# MotorBoard.net
KiCad netlist of a schematic drawn in EAGLE
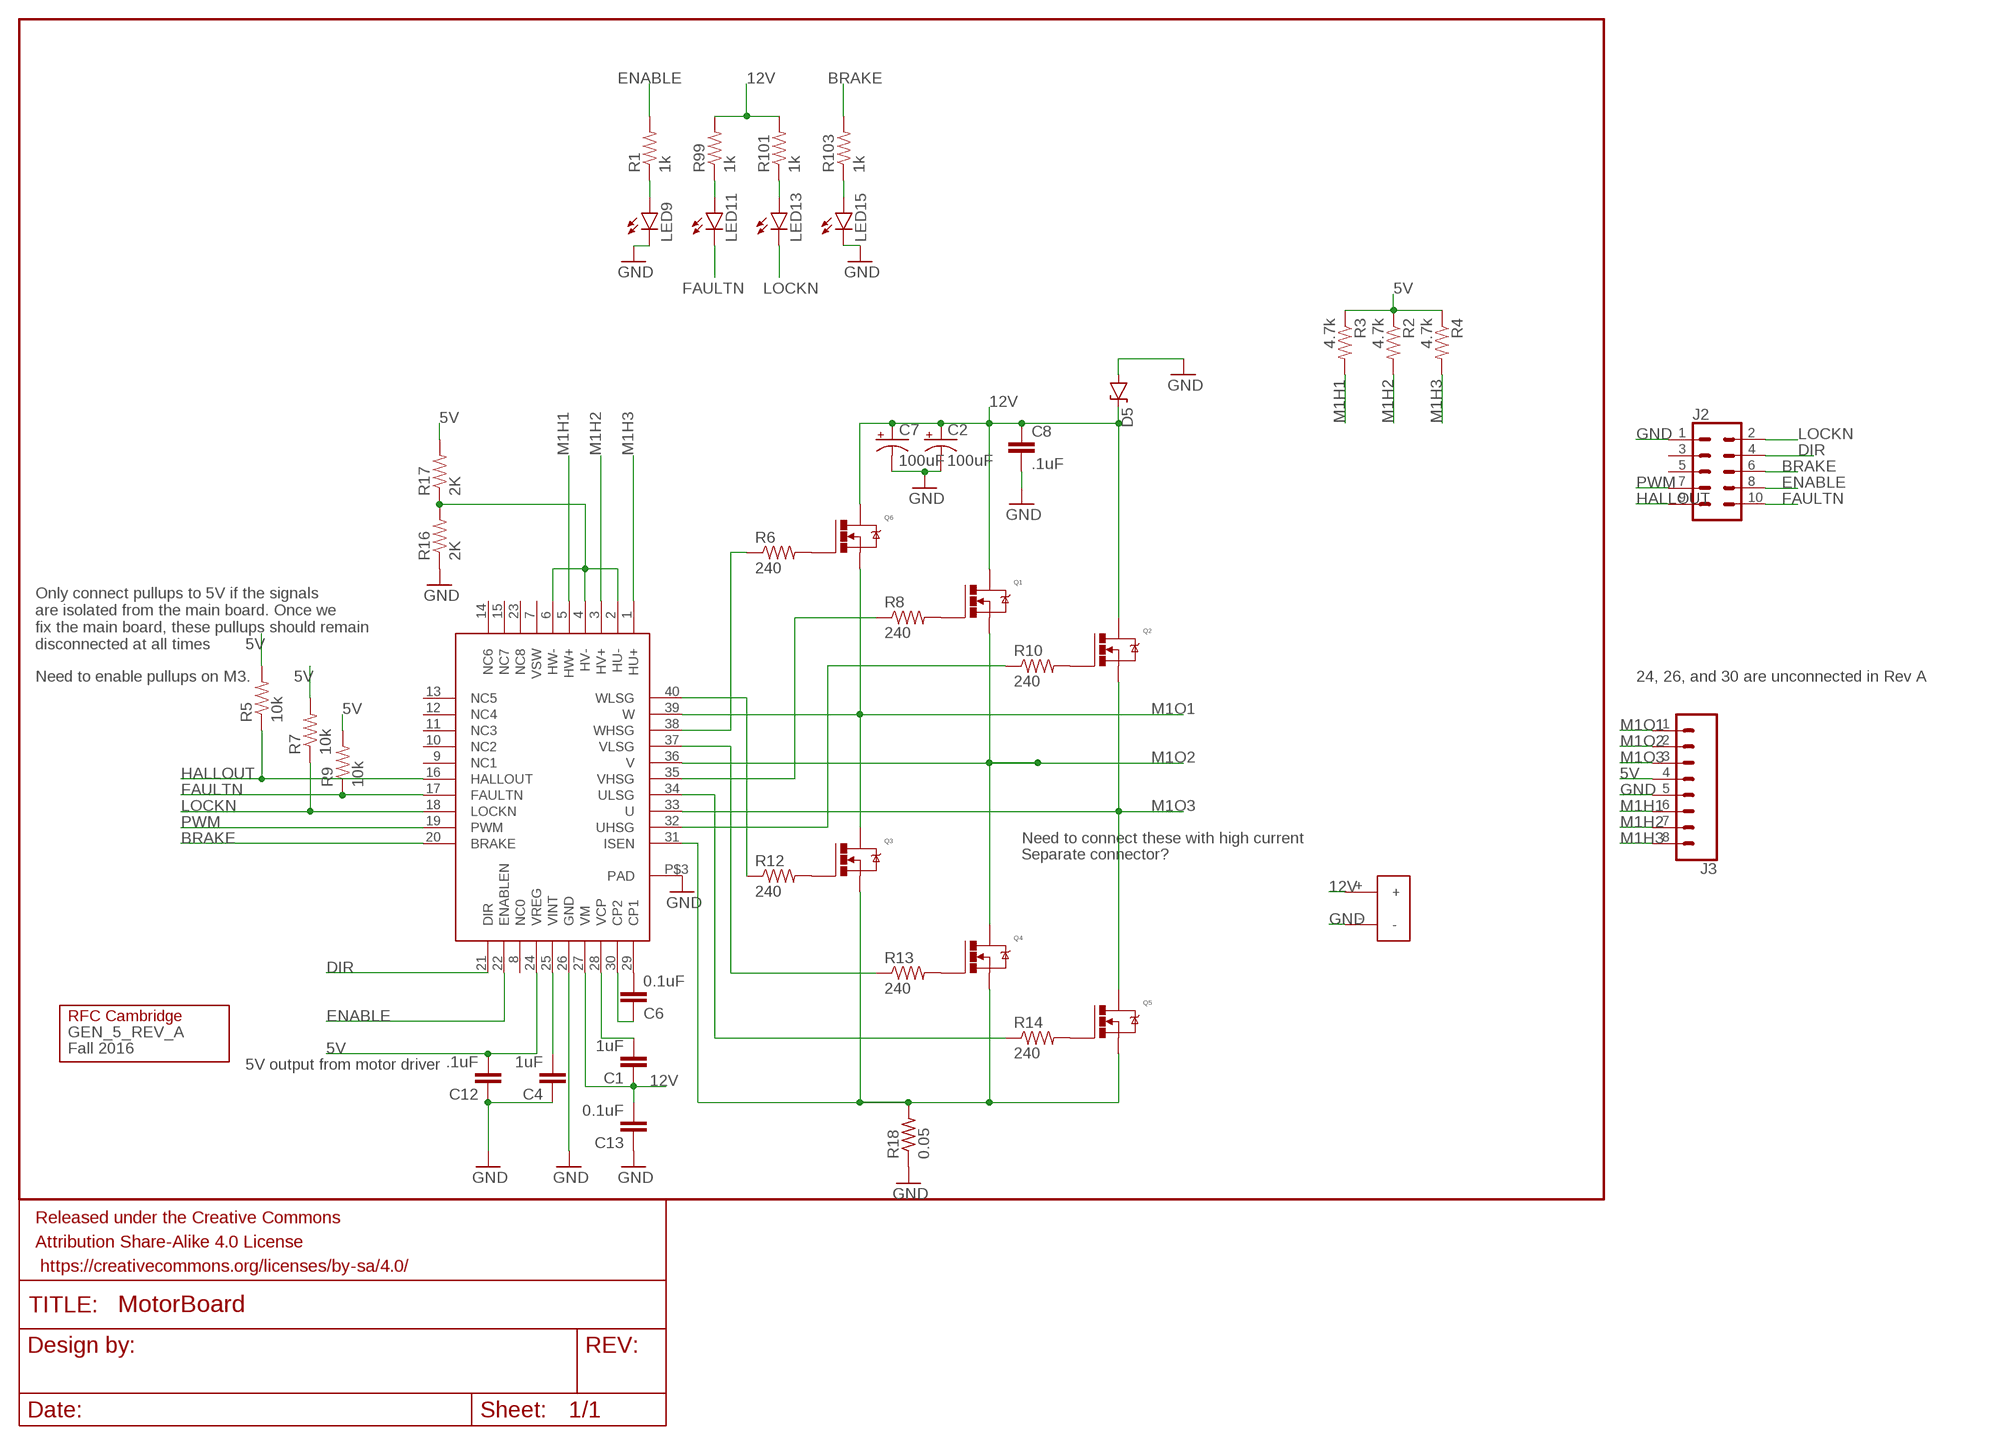
[diagram p0: schematic, sheet 1]

(export (version "E")
  (design (tool "Eeschema 10.0.6"))
  (components
    (comp (ref "C1")
      (value "1uF")
      (footprint "eagle-import:0805")
      (libsource (lib "eagle-import") (part "CAP0805"))
    )
    (comp (ref "C2")
      (value "100uF")
      (footprint "eagle-import:PANASONIC_D")
      (libsource (lib "eagle-import") (part "CAP-POLAR"))
    )
    (comp (ref "C4")
      (value "1uF")
      (footprint "eagle-import:0805")
      (libsource (lib "eagle-import") (part "CAP0805"))
    )
    (comp (ref "C6")
      (value "0.1uF")
      (footprint "eagle-import:0805")
      (libsource (lib "eagle-import") (part "CAP0805"))
    )
    (comp (ref "C7")
      (value "100uF")
      (footprint "eagle-import:PANASONIC_D")
      (libsource (lib "eagle-import") (part "CAP-POLAR"))
    )
    (comp (ref "C8")
      (value ".1uF")
      (footprint "eagle-import:0805")
      (libsource (lib "eagle-import") (part "CAP0805"))
    )
    (comp (ref "C12")
      (value ".1uF")
      (footprint "eagle-import:0805")
      (libsource (lib "eagle-import") (part "CAP0805"))
    )
    (comp (ref "C13")
      (value "0.1uF")
      (footprint "eagle-import:0805")
      (libsource (lib "eagle-import") (part "CAP0805"))
    )
    (comp (ref "D5")
      (value "DIODE-ZENERDO214AC")
      (footprint "eagle-import:DO214AC")
      (libsource (lib "eagle-import") (part "DIODE-ZENERDO214AC"))
    )
    (comp (ref "FRAME7")
      (value "FRAME-LETTER")
      (footprint "eagle-import:CREATIVE_COMMONS")
      (libsource (lib "eagle-import") (part "FRAME-LETTER"))
    )
    (comp (ref "GEN_5_REV_A")
      (value "Fall 2016")
      (footprint "eagle-import:LOGO")
      (libsource (lib "eagle-import") (part "LOGO"))
    )
    (comp (ref "J2")
      (value "CONN_05X2SHD")
      (footprint "eagle-import:2X5-SHROUDED")
      (libsource (lib "eagle-import") (part "CONN_05X2SHD"))
    )
    (comp (ref "J3")
      (value "CONN_08LONGPADS")
      (footprint "eagle-import:1X08_LONGPADS")
      (libsource (lib "eagle-import") (part "CONN_08LONGPADS"))
    )
    (comp (ref "LED9")
      (value "LED1206")
      (footprint "eagle-import:LED-1206")
      (libsource (lib "eagle-import") (part "LED1206"))
    )
    (comp (ref "LED11")
      (value "LED1206")
      (footprint "eagle-import:LED-1206")
      (libsource (lib "eagle-import") (part "LED1206"))
    )
    (comp (ref "LED13")
      (value "LED1206")
      (footprint "eagle-import:LED-1206")
      (libsource (lib "eagle-import") (part "LED1206"))
    )
    (comp (ref "LED15")
      (value "LED1206")
      (footprint "eagle-import:LED-1206")
      (libsource (lib "eagle-import") (part "LED1206"))
    )
    (comp (ref "Q1")
      (value "N-MOSFET")
      (footprint "eagle-import:DPAK")
      (libsource (lib "eagle-import") (part "N-MOSFET"))
    )
    (comp (ref "Q2")
      (value "N-MOSFET")
      (footprint "eagle-import:DPAK")
      (libsource (lib "eagle-import") (part "N-MOSFET"))
    )
    (comp (ref "Q3")
      (value "N-MOSFET")
      (footprint "eagle-import:DPAK")
      (libsource (lib "eagle-import") (part "N-MOSFET"))
    )
    (comp (ref "Q4")
      (value "N-MOSFET")
      (footprint "eagle-import:DPAK")
      (libsource (lib "eagle-import") (part "N-MOSFET"))
    )
    (comp (ref "Q5")
      (value "N-MOSFET")
      (footprint "eagle-import:DPAK")
      (libsource (lib "eagle-import") (part "N-MOSFET"))
    )
    (comp (ref "Q6")
      (value "N-MOSFET")
      (footprint "eagle-import:DPAK")
      (libsource (lib "eagle-import") (part "N-MOSFET"))
    )
    (comp (ref "R1")
      (value "1k")
      (footprint "eagle-import:0805")
      (libsource (lib "eagle-import") (part "RESISTOR0805-RES"))
    )
    (comp (ref "R2")
      (value "4.7k")
      (footprint "eagle-import:0805")
      (libsource (lib "eagle-import") (part "SparkFun-Resistors_RESISTOR0805-RES"))
    )
    (comp (ref "R3")
      (value "4.7k")
      (footprint "eagle-import:0805")
      (libsource (lib "eagle-import") (part "SparkFun-Resistors_RESISTOR0805-RES"))
    )
    (comp (ref "R4")
      (value "4.7k")
      (footprint "eagle-import:0805")
      (libsource (lib "eagle-import") (part "SparkFun-Resistors_RESISTOR0805-RES"))
    )
    (comp (ref "R5")
      (value "10k")
      (footprint "eagle-import:0805")
      (libsource (lib "eagle-import") (part "SparkFun-Resistors_RESISTOR0805-RES"))
    )
    (comp (ref "R6")
      (value "240")
      (footprint "eagle-import:0805")
      (libsource (lib "eagle-import") (part "SparkFun-Resistors_RESISTOR0805-RES"))
    )
    (comp (ref "R7")
      (value "10k")
      (footprint "eagle-import:0805")
      (libsource (lib "eagle-import") (part "SparkFun-Resistors_RESISTOR0805-RES"))
    )
    (comp (ref "R8")
      (value "240")
      (footprint "eagle-import:0805")
      (libsource (lib "eagle-import") (part "SparkFun-Resistors_RESISTOR0805-RES"))
    )
    (comp (ref "R9")
      (value "10k")
      (footprint "eagle-import:0805")
      (libsource (lib "eagle-import") (part "SparkFun-Resistors_RESISTOR0805-RES"))
    )
    (comp (ref "R10")
      (value "240")
      (footprint "eagle-import:0805")
      (libsource (lib "eagle-import") (part "SparkFun-Resistors_RESISTOR0805-RES"))
    )
    (comp (ref "R12")
      (value "240")
      (footprint "eagle-import:0805")
      (libsource (lib "eagle-import") (part "SparkFun-Resistors_RESISTOR0805-RES"))
    )
    (comp (ref "R13")
      (value "240")
      (footprint "eagle-import:0805")
      (libsource (lib "eagle-import") (part "SparkFun-Resistors_RESISTOR0805-RES"))
    )
    (comp (ref "R14")
      (value "240")
      (footprint "eagle-import:0805")
      (libsource (lib "eagle-import") (part "SparkFun-Resistors_RESISTOR0805-RES"))
    )
    (comp (ref "R16")
      (value "2K")
      (footprint "eagle-import:0805")
      (libsource (lib "eagle-import") (part "SparkFun-Resistors_RESISTOR0805-RES"))
    )
    (comp (ref "R17")
      (value "2K")
      (footprint "eagle-import:0805")
      (libsource (lib "eagle-import") (part "SparkFun-Resistors_RESISTOR0805-RES"))
    )
    (comp (ref "R18")
      (value "0.05")
      (footprint "eagle-import:R2512")
      (libsource (lib "eagle-import") (part "R-US_R2512"))
    )
    (comp (ref "R99")
      (value "1k")
      (footprint "eagle-import:0805")
      (libsource (lib "eagle-import") (part "RESISTOR0805-RES"))
    )
    (comp (ref "R101")
      (value "1k")
      (footprint "eagle-import:0805")
      (libsource (lib "eagle-import") (part "RESISTOR0805-RES"))
    )
    (comp (ref "R103")
      (value "1k")
      (footprint "eagle-import:0805")
      (libsource (lib "eagle-import") (part "RESISTOR0805-RES"))
    )
    (comp (ref "U$1")
      (value "DRV8307")
      (footprint "eagle-import:QFN40-6X6")
      (libsource (lib "eagle-import") (part "DRV8307"))
    )
    (comp (ref "U$2")
      (value "POWER_CONN_2X1")
      (footprint "eagle-import:POWER_CONN_2X1")
      (libsource (lib "eagle-import") (part "POWER_CONN_2X1"))
    )
  )
  (nets
    (net (code "1") (name "/5V") (class "Default")
      (node (ref "C12") (pin "2") (pinfunction "2_2") (pintype "passive"))
      (node (ref "J3") (pin "4") (pinfunction "4_4") (pintype "passive"))
      (node (ref "R17") (pin "2") (pinfunction "2_2") (pintype "passive"))
      (node (ref "R2") (pin "1") (pinfunction "1_1") (pintype "passive"))
      (node (ref "R3") (pin "1") (pinfunction "1_1") (pintype "passive"))
      (node (ref "R4") (pin "1") (pinfunction "1_1") (pintype "passive"))
      (node (ref "R5") (pin "2") (pinfunction "2_2") (pintype "passive"))
      (node (ref "R7") (pin "2") (pinfunction "2_2") (pintype "passive"))
      (node (ref "R9") (pin "2") (pinfunction "2_2") (pintype "passive"))
      (node (ref "U$1") (pin "24") (pinfunction "VREG_24") (pintype "bidirectional"))
    )
    (net (code "2") (name "/12V") (class "Default")
      (node (ref "C1") (pin "1") (pinfunction "1_1") (pintype "passive"))
      (node (ref "C13") (pin "2") (pinfunction "2_2") (pintype "passive"))
      (node (ref "C2") (pin "+") (pinfunction "+_+") (pintype "passive"))
      (node (ref "C7") (pin "+") (pinfunction "+_+") (pintype "passive"))
      (node (ref "C8") (pin "1") (pinfunction "1_1") (pintype "passive"))
      (node (ref "D5") (pin "C") (pinfunction "C_C") (pintype "passive"))
      (node (ref "Q1") (pin "DRAIN") (pinfunction "P$1_DRAIN") (pintype "bidirectional"))
      (node (ref "Q2") (pin "DRAIN") (pinfunction "P$1_DRAIN") (pintype "bidirectional"))
      (node (ref "Q6") (pin "DRAIN") (pinfunction "P$1_DRAIN") (pintype "bidirectional"))
      (node (ref "R101") (pin "2") (pinfunction "2_2") (pintype "passive"))
      (node (ref "R99") (pin "2") (pinfunction "2_2") (pintype "passive"))
      (node (ref "U$1") (pin "27") (pinfunction "VM_27") (pintype "bidirectional"))
      (node (ref "U$2") (pin "+") (pinfunction "+_+") (pintype "bidirectional"))
    )
    (net (code "3") (name "/BRAKE") (class "Default")
      (node (ref "J2") (pin "6") (pinfunction "6_6") (pintype "passive"))
      (node (ref "R103") (pin "2") (pinfunction "2_2") (pintype "passive"))
      (node (ref "U$1") (pin "20") (pinfunction "BRAKE_20") (pintype "bidirectional"))
    )
    (net (code "4") (name "/DIR") (class "Default")
      (node (ref "J2") (pin "4") (pinfunction "4_4") (pintype "passive"))
      (node (ref "U$1") (pin "21") (pinfunction "DIR_21") (pintype "bidirectional"))
    )
    (net (code "5") (name "/ENABLE") (class "Default")
      (node (ref "J2") (pin "8") (pinfunction "8_8") (pintype "passive"))
      (node (ref "R1") (pin "2") (pinfunction "2_2") (pintype "passive"))
      (node (ref "U$1") (pin "22") (pinfunction "ENABLEN_22") (pintype "bidirectional"))
    )
    (net (code "6") (name "/FAULTN") (class "Default")
      (node (ref "J2") (pin "10") (pinfunction "10_10") (pintype "passive"))
      (node (ref "LED11") (pin "C") (pinfunction "C_C") (pintype "passive"))
      (node (ref "R9") (pin "1") (pinfunction "1_1") (pintype "passive"))
      (node (ref "U$1") (pin "17") (pinfunction "FAULTN_17") (pintype "bidirectional"))
    )
    (net (code "7") (name "/HALLOUT") (class "Default")
      (node (ref "J2") (pin "9") (pinfunction "9_9") (pintype "passive"))
      (node (ref "R5") (pin "1") (pinfunction "1_1") (pintype "passive"))
      (node (ref "U$1") (pin "16") (pinfunction "HALLOUT_16") (pintype "bidirectional"))
    )
    (net (code "8") (name "/LOCKN") (class "Default")
      (node (ref "J2") (pin "2") (pinfunction "2_2") (pintype "passive"))
      (node (ref "LED13") (pin "C") (pinfunction "C_C") (pintype "passive"))
      (node (ref "R7") (pin "1") (pinfunction "1_1") (pintype "passive"))
      (node (ref "U$1") (pin "18") (pinfunction "LOCKN_18") (pintype "bidirectional"))
    )
    (net (code "9") (name "/M1H1") (class "Default")
      (node (ref "J3") (pin "6") (pinfunction "6_6") (pintype "passive"))
      (node (ref "R3") (pin "2") (pinfunction "2_2") (pintype "passive"))
      (node (ref "U$1") (pin "5") (pinfunction "HW+_5") (pintype "bidirectional"))
    )
    (net (code "10") (name "/M1H2") (class "Default")
      (node (ref "J3") (pin "7") (pinfunction "7_7") (pintype "passive"))
      (node (ref "R2") (pin "2") (pinfunction "2_2") (pintype "passive"))
      (node (ref "U$1") (pin "3") (pinfunction "HV+_3") (pintype "bidirectional"))
    )
    (net (code "11") (name "/M1H3") (class "Default")
      (node (ref "J3") (pin "8") (pinfunction "8_8") (pintype "passive"))
      (node (ref "R4") (pin "2") (pinfunction "2_2") (pintype "passive"))
      (node (ref "U$1") (pin "1") (pinfunction "HU+_1") (pintype "bidirectional"))
    )
    (net (code "12") (name "/M1O1") (class "Default")
      (node (ref "J3") (pin "1") (pinfunction "1_1") (pintype "passive"))
      (node (ref "Q3") (pin "DRAIN") (pinfunction "P$1_DRAIN") (pintype "bidirectional"))
      (node (ref "Q6") (pin "SOURCE") (pinfunction "P$2_SOURCE") (pintype "bidirectional"))
      (node (ref "U$1") (pin "39") (pinfunction "W_39") (pintype "bidirectional"))
    )
    (net (code "13") (name "/M1O2") (class "Default")
      (node (ref "J3") (pin "2") (pinfunction "2_2") (pintype "passive"))
      (node (ref "Q1") (pin "SOURCE") (pinfunction "P$2_SOURCE") (pintype "bidirectional"))
      (node (ref "Q4") (pin "DRAIN") (pinfunction "P$1_DRAIN") (pintype "bidirectional"))
      (node (ref "U$1") (pin "36") (pinfunction "V_36") (pintype "bidirectional"))
    )
    (net (code "14") (name "/M1O3") (class "Default")
      (node (ref "J3") (pin "3") (pinfunction "3_3") (pintype "passive"))
      (node (ref "Q2") (pin "SOURCE") (pinfunction "P$2_SOURCE") (pintype "bidirectional"))
      (node (ref "Q5") (pin "DRAIN") (pinfunction "P$1_DRAIN") (pintype "bidirectional"))
      (node (ref "U$1") (pin "33") (pinfunction "U_33") (pintype "bidirectional"))
    )
    (net (code "15") (name "/PWM") (class "Default")
      (node (ref "J2") (pin "7") (pinfunction "7_7") (pintype "passive"))
      (node (ref "U$1") (pin "19") (pinfunction "PWM_19") (pintype "bidirectional"))
    )
    (net (code "16") (name "GND") (class "Default")
      (node (ref "C12") (pin "1") (pinfunction "1_1") (pintype "passive"))
      (node (ref "C13") (pin "1") (pinfunction "1_1") (pintype "passive"))
      (node (ref "C2") (pin "-") (pinfunction "-_-") (pintype "passive"))
      (node (ref "C4") (pin "1") (pinfunction "1_1") (pintype "passive"))
      (node (ref "C7") (pin "-") (pinfunction "-_-") (pintype "passive"))
      (node (ref "C8") (pin "2") (pinfunction "2_2") (pintype "passive"))
      (node (ref "D5") (pin "A") (pinfunction "A_A") (pintype "passive"))
      (node (ref "J2") (pin "1") (pinfunction "1_1") (pintype "passive"))
      (node (ref "J3") (pin "5") (pinfunction "5_5") (pintype "passive"))
      (node (ref "LED15") (pin "C") (pinfunction "C_C") (pintype "passive"))
      (node (ref "LED9") (pin "C") (pinfunction "C_C") (pintype "passive"))
      (node (ref "R16") (pin "1") (pinfunction "1_1") (pintype "passive"))
      (node (ref "R18") (pin "1") (pinfunction "1_1") (pintype "passive"))
      (node (ref "U$1") (pin "26") (pinfunction "GND_26") (pintype "bidirectional"))
      (node (ref "U$1") (pin "P$3") (pinfunction "PAD_P$3") (pintype "bidirectional"))
      (node (ref "U$2") (pin "-") (pinfunction "-_-") (pintype "bidirectional"))
    )
    (net (code "17") (name "Net-(LED9-PadA)") (class "Default")
      (node (ref "LED9") (pin "A") (pinfunction "A_A") (pintype "passive"))
      (node (ref "R1") (pin "1") (pinfunction "1_1") (pintype "passive"))
    )
    (net (code "18") (name "Net-(LED11-PadA)") (class "Default")
      (node (ref "LED11") (pin "A") (pinfunction "A_A") (pintype "passive"))
      (node (ref "R99") (pin "1") (pinfunction "1_1") (pintype "passive"))
    )
    (net (code "19") (name "Net-(LED13-PadA)") (class "Default")
      (node (ref "LED13") (pin "A") (pinfunction "A_A") (pintype "passive"))
      (node (ref "R101") (pin "1") (pinfunction "1_1") (pintype "passive"))
    )
    (net (code "20") (name "Net-(LED15-PadA)") (class "Default")
      (node (ref "LED15") (pin "A") (pinfunction "A_A") (pintype "passive"))
      (node (ref "R103") (pin "1") (pinfunction "1_1") (pintype "passive"))
    )
    (net (code "21") (name "Net-(Q1-P$3)") (class "Default")
      (node (ref "Q1") (pin "GATE") (pinfunction "P$3_GATE") (pintype "bidirectional"))
      (node (ref "R8") (pin "2") (pinfunction "2_2") (pintype "passive"))
    )
    (net (code "22") (name "Net-(Q2-P$3)") (class "Default")
      (node (ref "Q2") (pin "GATE") (pinfunction "P$3_GATE") (pintype "bidirectional"))
      (node (ref "R10") (pin "2") (pinfunction "2_2") (pintype "passive"))
    )
    (net (code "23") (name "Net-(Q3-P$2)") (class "Default")
      (node (ref "Q3") (pin "SOURCE") (pinfunction "P$2_SOURCE") (pintype "bidirectional"))
      (node (ref "Q4") (pin "SOURCE") (pinfunction "P$2_SOURCE") (pintype "bidirectional"))
      (node (ref "Q5") (pin "SOURCE") (pinfunction "P$2_SOURCE") (pintype "bidirectional"))
      (node (ref "R18") (pin "2") (pinfunction "2_2") (pintype "passive"))
      (node (ref "U$1") (pin "31") (pinfunction "ISEN_31") (pintype "bidirectional"))
    )
    (net (code "24") (name "Net-(Q3-P$3)") (class "Default")
      (node (ref "Q3") (pin "GATE") (pinfunction "P$3_GATE") (pintype "bidirectional"))
      (node (ref "R12") (pin "2") (pinfunction "2_2") (pintype "passive"))
    )
    (net (code "25") (name "Net-(Q4-P$3)") (class "Default")
      (node (ref "Q4") (pin "GATE") (pinfunction "P$3_GATE") (pintype "bidirectional"))
      (node (ref "R13") (pin "2") (pinfunction "2_2") (pintype "passive"))
    )
    (net (code "26") (name "Net-(Q5-P$3)") (class "Default")
      (node (ref "Q5") (pin "GATE") (pinfunction "P$3_GATE") (pintype "bidirectional"))
      (node (ref "R14") (pin "2") (pinfunction "2_2") (pintype "passive"))
    )
    (net (code "27") (name "Net-(Q6-P$3)") (class "Default")
      (node (ref "Q6") (pin "GATE") (pinfunction "P$3_GATE") (pintype "bidirectional"))
      (node (ref "R6") (pin "2") (pinfunction "2_2") (pintype "passive"))
    )
    (net (code "28") (name "Net-(U$1-CP1)") (class "Default")
      (node (ref "C6") (pin "2") (pinfunction "2_2") (pintype "passive"))
      (node (ref "U$1") (pin "29") (pinfunction "CP1_29") (pintype "bidirectional"))
    )
    (net (code "29") (name "Net-(U$1-CP2)") (class "Default")
      (node (ref "C6") (pin "1") (pinfunction "1_1") (pintype "passive"))
      (node (ref "U$1") (pin "30") (pinfunction "CP2_30") (pintype "bidirectional"))
    )
    (net (code "30") (name "Net-(U$1-HU-)") (class "Default")
      (node (ref "R16") (pin "2") (pinfunction "2_2") (pintype "passive"))
      (node (ref "R17") (pin "1") (pinfunction "1_1") (pintype "passive"))
      (node (ref "U$1") (pin "2") (pinfunction "HU-_2") (pintype "bidirectional"))
      (node (ref "U$1") (pin "4") (pinfunction "HV-_4") (pintype "bidirectional"))
      (node (ref "U$1") (pin "6") (pinfunction "HW-_6") (pintype "bidirectional"))
    )
    (net (code "31") (name "Net-(U$1-UHSG)") (class "Default")
      (node (ref "R10") (pin "1") (pinfunction "1_1") (pintype "passive"))
      (node (ref "U$1") (pin "32") (pinfunction "UHSG_32") (pintype "bidirectional"))
    )
    (net (code "32") (name "Net-(U$1-ULSG)") (class "Default")
      (node (ref "R14") (pin "1") (pinfunction "1_1") (pintype "passive"))
      (node (ref "U$1") (pin "34") (pinfunction "ULSG_34") (pintype "bidirectional"))
    )
    (net (code "33") (name "Net-(U$1-VCP)") (class "Default")
      (node (ref "C1") (pin "2") (pinfunction "2_2") (pintype "passive"))
      (node (ref "U$1") (pin "28") (pinfunction "VCP_28") (pintype "bidirectional"))
    )
    (net (code "34") (name "Net-(U$1-VHSG)") (class "Default")
      (node (ref "R8") (pin "1") (pinfunction "1_1") (pintype "passive"))
      (node (ref "U$1") (pin "35") (pinfunction "VHSG_35") (pintype "bidirectional"))
    )
    (net (code "35") (name "Net-(U$1-VINT)") (class "Default")
      (node (ref "C4") (pin "2") (pinfunction "2_2") (pintype "passive"))
      (node (ref "U$1") (pin "25") (pinfunction "VINT_25") (pintype "bidirectional"))
    )
    (net (code "36") (name "Net-(U$1-VLSG)") (class "Default")
      (node (ref "R13") (pin "1") (pinfunction "1_1") (pintype "passive"))
      (node (ref "U$1") (pin "37") (pinfunction "VLSG_37") (pintype "bidirectional"))
    )
    (net (code "37") (name "Net-(U$1-WHSG)") (class "Default")
      (node (ref "R6") (pin "1") (pinfunction "1_1") (pintype "passive"))
      (node (ref "U$1") (pin "38") (pinfunction "WHSG_38") (pintype "bidirectional"))
    )
    (net (code "38") (name "Net-(U$1-WLSG)") (class "Default")
      (node (ref "R12") (pin "1") (pinfunction "1_1") (pintype "passive"))
      (node (ref "U$1") (pin "40") (pinfunction "WLSG_40") (pintype "bidirectional"))
    )
    (net (code "39") (name "unconnected-(J2-Pad3)") (class "Default")
      (node (ref "J2") (pin "3") (pinfunction "3_3") (pintype "passive"))
    )
    (net (code "40") (name "unconnected-(J2-Pad5)") (class "Default")
      (node (ref "J2") (pin "5") (pinfunction "5_5") (pintype "passive"))
    )
    (net (code "41") (name "unconnected-(U$1-NC0-Pad8)") (class "Default")
      (node (ref "U$1") (pin "8") (pinfunction "NC0_8") (pintype "bidirectional"))
    )
    (net (code "42") (name "unconnected-(U$1-NC1-Pad9)") (class "Default")
      (node (ref "U$1") (pin "9") (pinfunction "NC1_9") (pintype "bidirectional"))
    )
    (net (code "43") (name "unconnected-(U$1-NC2-Pad10)") (class "Default")
      (node (ref "U$1") (pin "10") (pinfunction "NC2_10") (pintype "bidirectional"))
    )
    (net (code "44") (name "unconnected-(U$1-NC3-Pad11)") (class "Default")
      (node (ref "U$1") (pin "11") (pinfunction "NC3_11") (pintype "bidirectional"))
    )
    (net (code "45") (name "unconnected-(U$1-NC4-Pad12)") (class "Default")
      (node (ref "U$1") (pin "12") (pinfunction "NC4_12") (pintype "bidirectional"))
    )
    (net (code "46") (name "unconnected-(U$1-NC5-Pad13)") (class "Default")
      (node (ref "U$1") (pin "13") (pinfunction "NC5_13") (pintype "bidirectional"))
    )
    (net (code "47") (name "unconnected-(U$1-NC6-Pad14)") (class "Default")
      (node (ref "U$1") (pin "14") (pinfunction "NC6_14") (pintype "bidirectional"))
    )
    (net (code "48") (name "unconnected-(U$1-NC7-Pad15)") (class "Default")
      (node (ref "U$1") (pin "15") (pinfunction "NC7_15") (pintype "bidirectional"))
    )
    (net (code "49") (name "unconnected-(U$1-NC8-Pad23)") (class "Default")
      (node (ref "U$1") (pin "23") (pinfunction "NC8_23") (pintype "bidirectional"))
    )
    (net (code "50") (name "unconnected-(U$1-VSW-Pad7)") (class "Default")
      (node (ref "U$1") (pin "7") (pinfunction "VSW_7") (pintype "bidirectional"))
    )
  )
)
